# MuroBox-USB.net
KiCad netlist of a schematic drawn in EAGLE
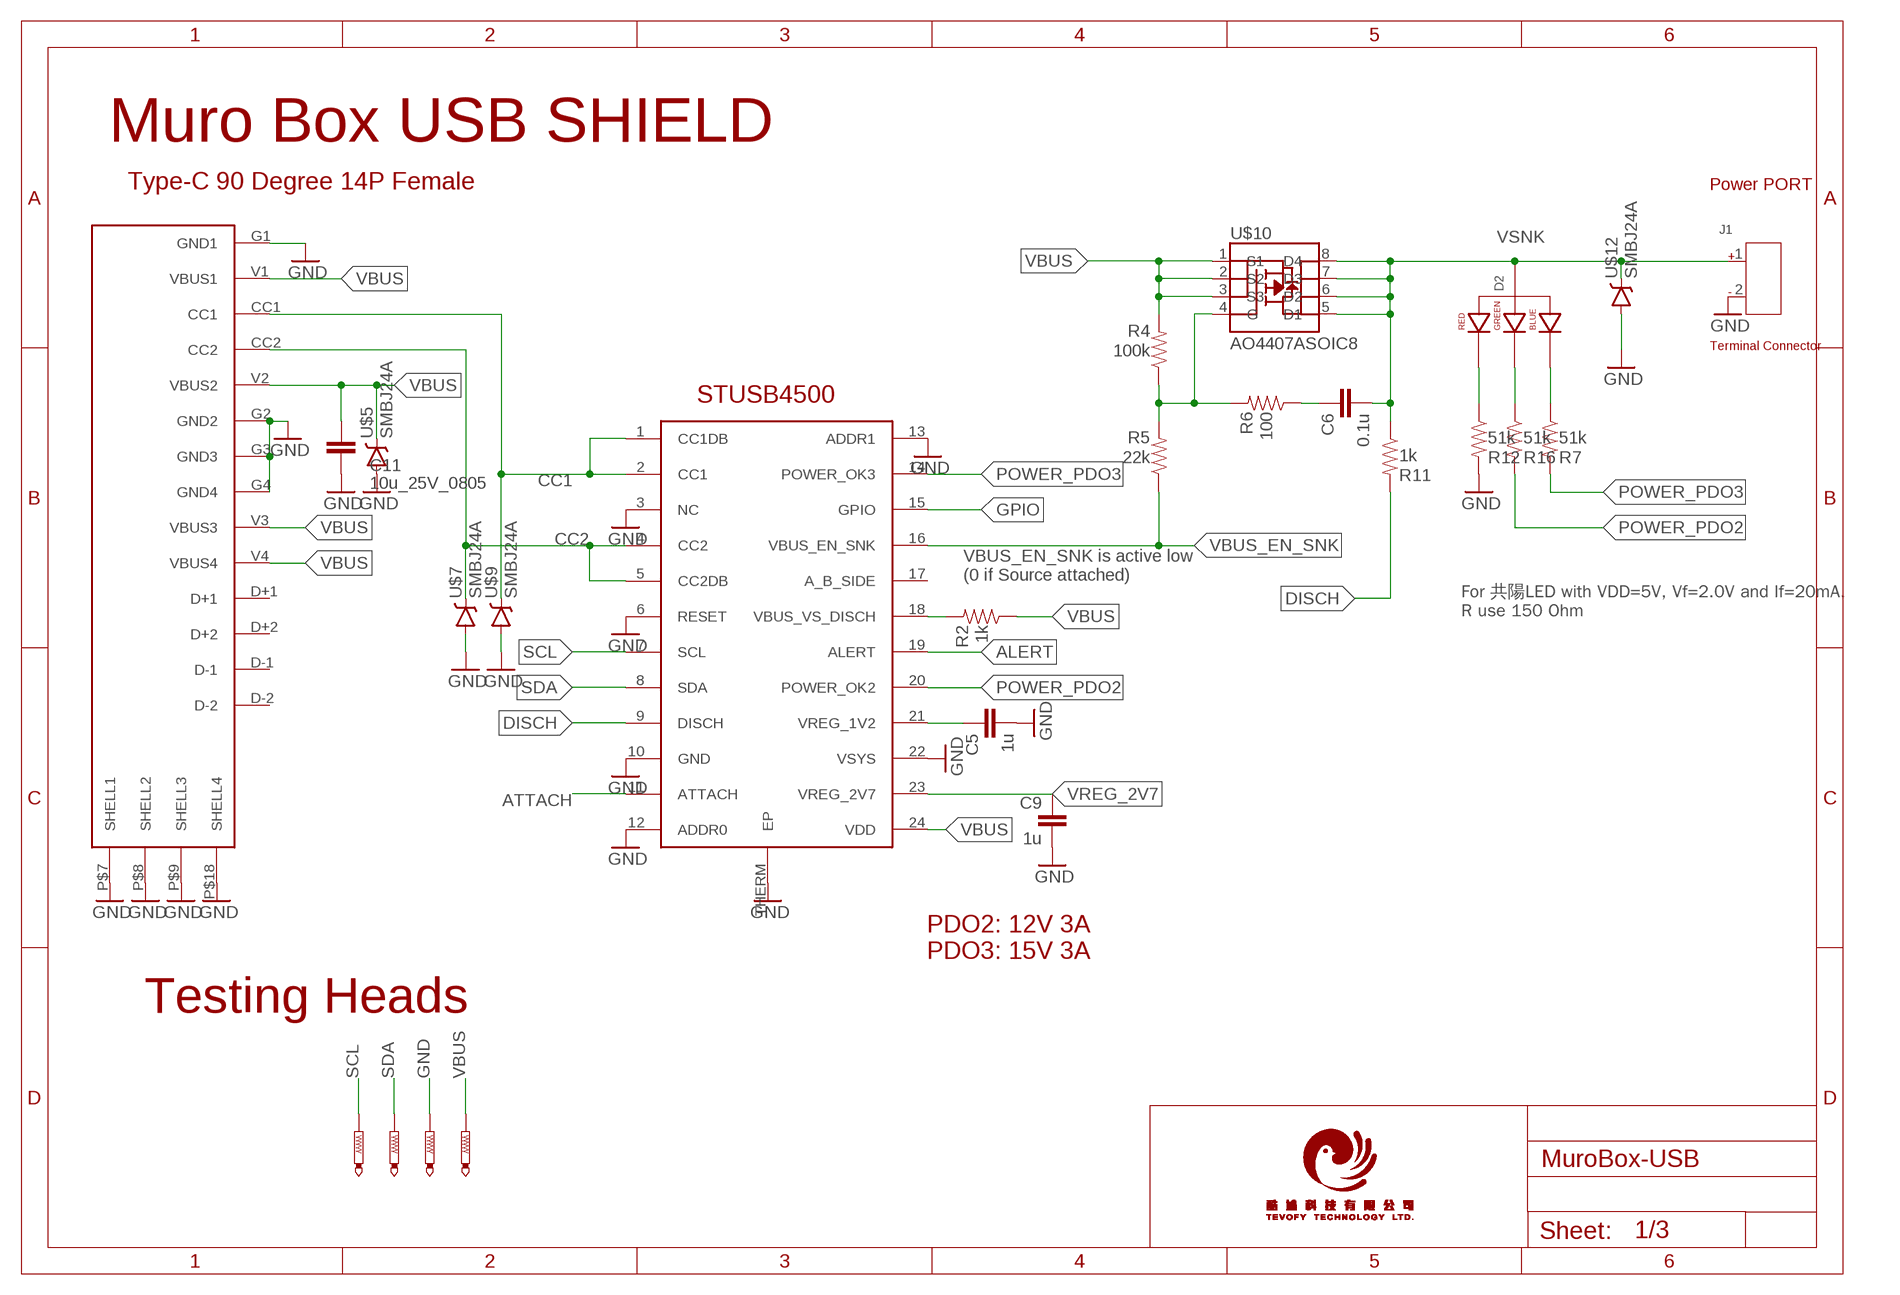
[diagram p0: schematic, sheet 1]
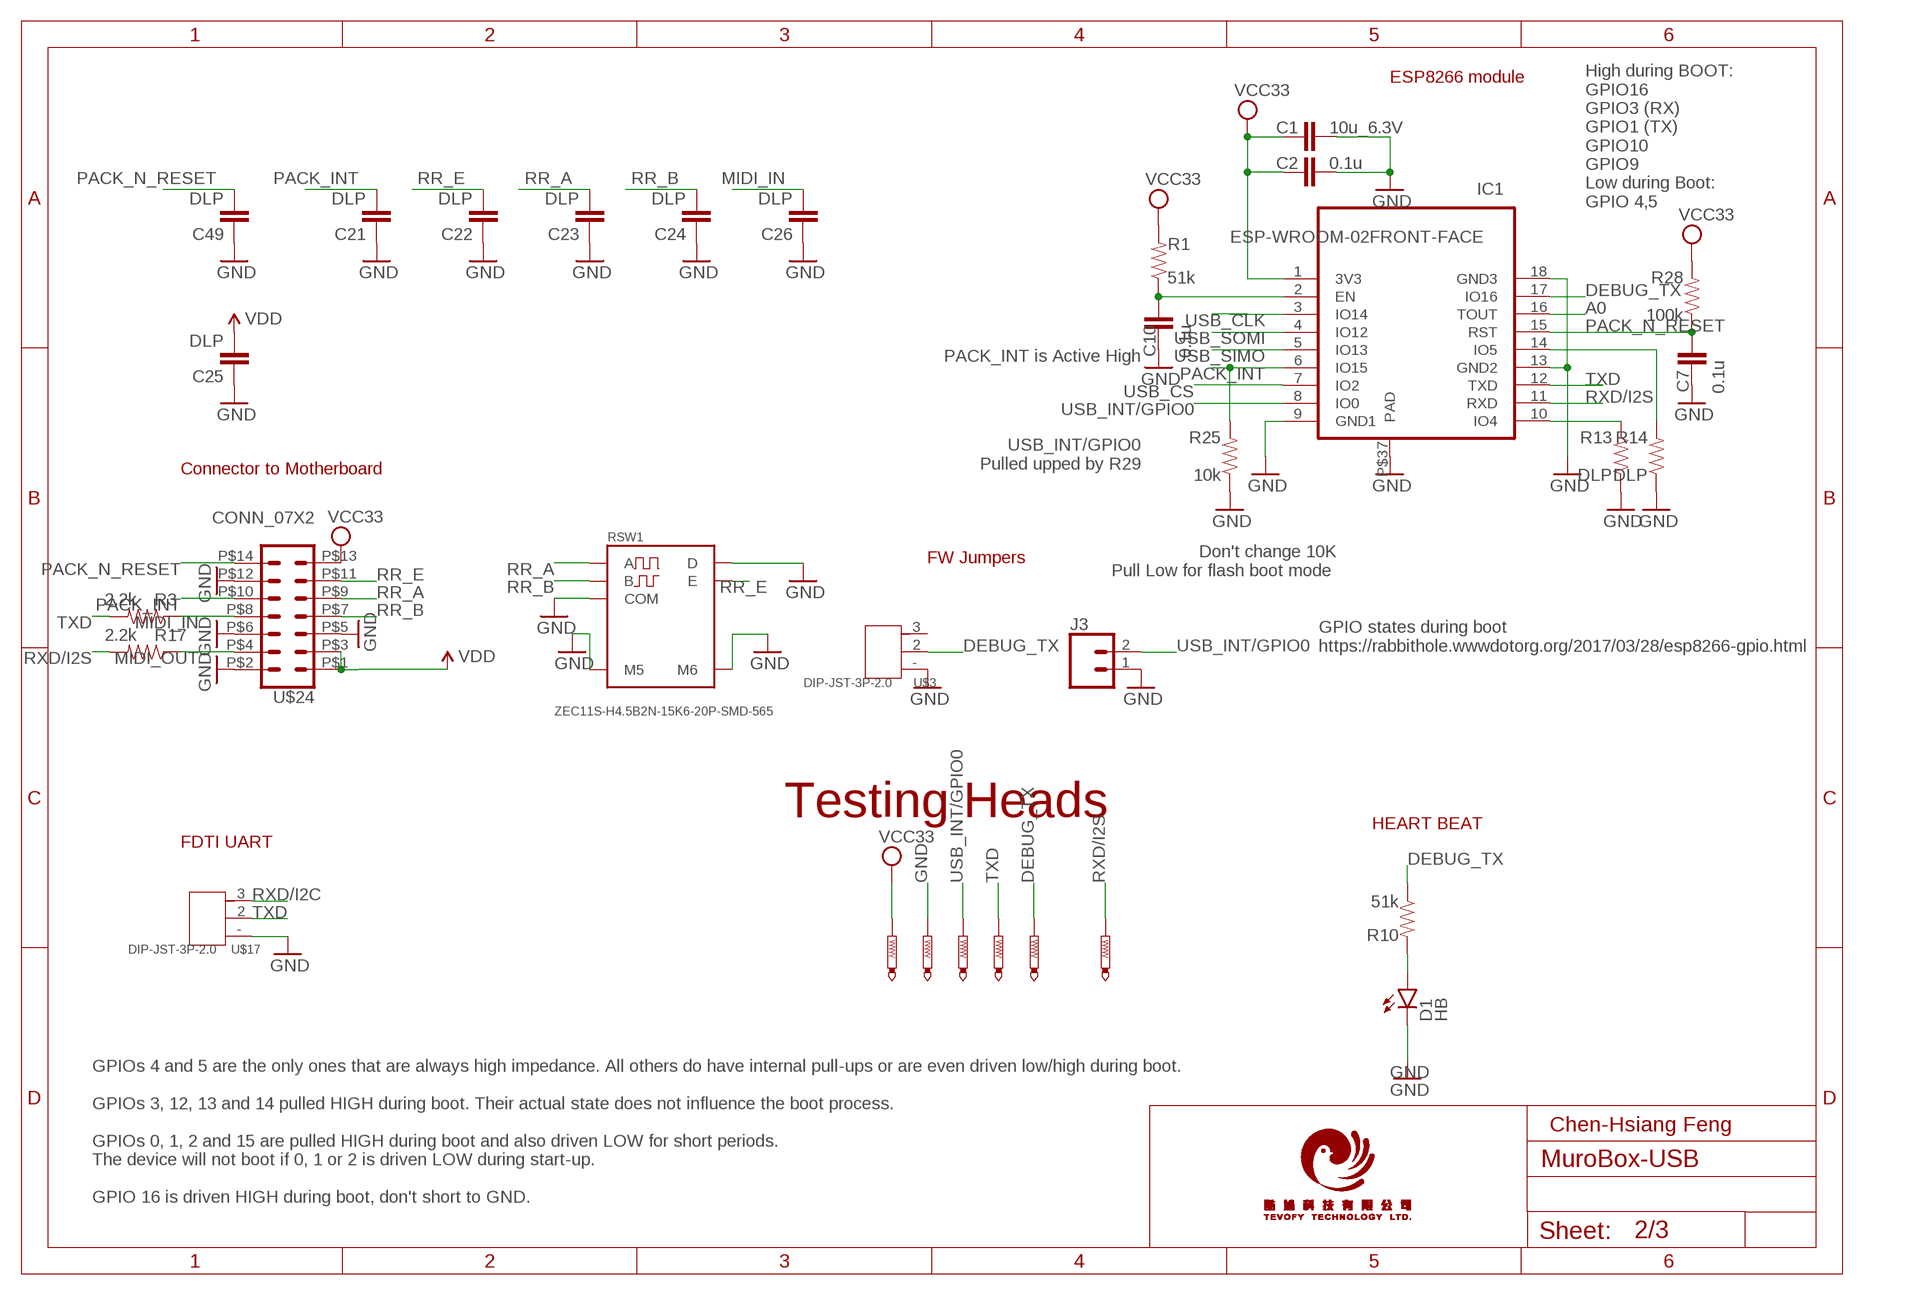
[diagram p1: schematic, sheet 2]
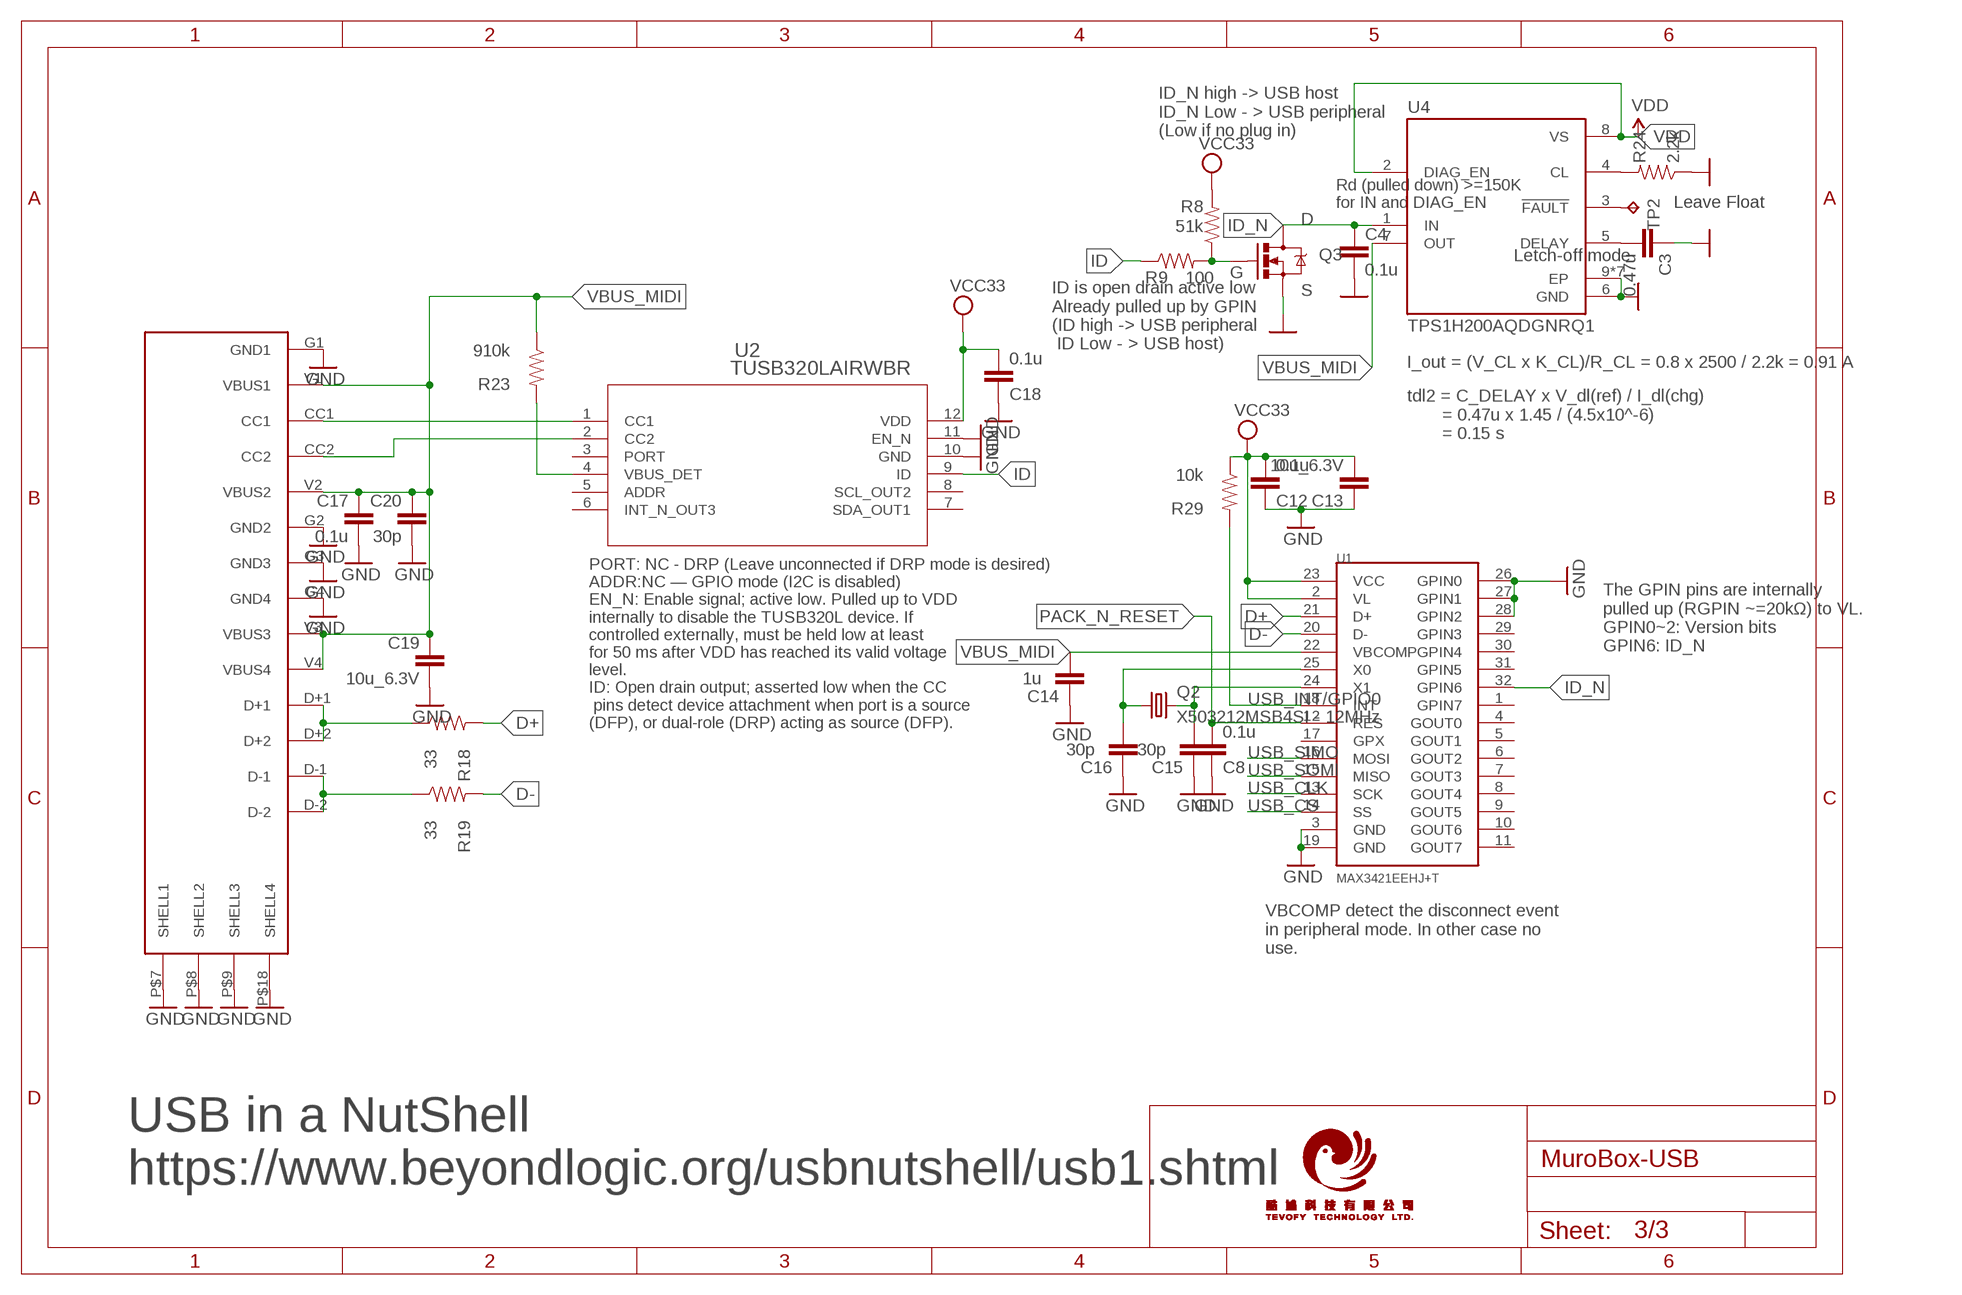
[diagram p2: schematic, sheet 3]

(export (version "E")
  (design (tool "Eeschema 10.0.6"))
  (components
    (comp (ref "C5")
      (value "1u")
      (footprint "eagle-import:0603-CAP")
      (libsource (lib "eagle-import") (part "CAP0603-CAP"))
    )
    (comp (ref "C6")
      (value "0.1u")
      (footprint "eagle-import:0603-CAP")
      (libsource (lib "eagle-import") (part "CAP0603-CAP"))
    )
    (comp (ref "C9")
      (value "1u")
      (footprint "eagle-import:0603-CAP")
      (libsource (lib "eagle-import") (part "CAP0603-CAP"))
    )
    (comp (ref "C11")
      (value "10u_25V_0805")
      (footprint "eagle-import:0805-CAP")
      (libsource (lib "eagle-import") (part "10UF10V10%(0805)"))
    )
    (comp (ref "D2")
      (value "LED-RGB-CA-THRUCLEAR")
      (footprint "eagle-import:LED-RGB-THRU")
      (libsource (lib "eagle-import") (part "LED-RGB-CA-THRUCLEAR"))
    )
    (comp (ref "J1")
      (value "DIP-SCREW-TERMINAL(2P-2.54)")
      (footprint "eagle-import:H2-2.54-5.48X6.3MM")
      (libsource (lib "eagle-import") (part "DIP-SCREW-TERMINAL(2P-2.54)"))
    )
    (comp (ref "R2")
      (value "1k")
      (footprint "eagle-import:0603-RES")
      (libsource (lib "eagle-import") (part "RESISTOR0603-RES"))
    )
    (comp (ref "R4")
      (value "100k")
      (footprint "eagle-import:0603-RES")
      (libsource (lib "eagle-import") (part "RESISTOR0603-RES"))
    )
    (comp (ref "R5")
      (value "22k")
      (footprint "eagle-import:0603-RES")
      (libsource (lib "eagle-import") (part "RESISTOR0603-RES"))
    )
    (comp (ref "R6")
      (value "100")
      (footprint "eagle-import:0603-RES")
      (libsource (lib "eagle-import") (part "RESISTOR0603-RES"))
    )
    (comp (ref "R7")
      (value "51k")
      (footprint "eagle-import:0603-RES")
      (libsource (lib "eagle-import") (part "RESISTOR0603-RES"))
    )
    (comp (ref "R11")
      (value "1k")
      (footprint "eagle-import:0603-RES")
      (libsource (lib "eagle-import") (part "RESISTOR0603-RES"))
    )
    (comp (ref "R12")
      (value "51k")
      (footprint "eagle-import:0603-RES")
      (libsource (lib "eagle-import") (part "RESISTOR0603-RES"))
    )
    (comp (ref "R16")
      (value "51k")
      (footprint "eagle-import:0603-RES")
      (libsource (lib "eagle-import") (part "RESISTOR0603-RES"))
    )
    (comp (ref "U$1")
      (value "STUSB4500")
      (footprint "eagle-import:QFN24")
      (libsource (lib "eagle-import") (part "STUSB4500"))
    )
    (comp (ref "U$5")
      (value "SMBJ24A")
      (footprint "eagle-import:SMB-DIODE")
      (libsource (lib "eagle-import") (part "SMBJ24A"))
    )
    (comp (ref "U$7")
      (value "SMBJ24A")
      (footprint "eagle-import:SMB-DIODE")
      (libsource (lib "eagle-import") (part "SMBJ24A"))
    )
    (comp (ref "U$9")
      (value "SMBJ24A")
      (footprint "eagle-import:SMB-DIODE")
      (libsource (lib "eagle-import") (part "SMBJ24A"))
    )
    (comp (ref "U$10")
      (value "AO4407ASOIC8")
      (footprint "eagle-import:SO08")
      (libsource (lib "eagle-import") (part "AO4407ASOIC8"))
    )
    (comp (ref "U$12")
      (value "SMBJ24A")
      (footprint "eagle-import:SMB-DIODE")
      (libsource (lib "eagle-import") (part "SMBJ24A"))
    )
    (comp (ref "U$22")
      (value "1PIN_TEST_PAD")
      (footprint "eagle-import:TP18R")
      (libsource (lib "eagle-import") (part "1PIN_TEST_PAD"))
    )
    (comp (ref "U$23")
      (value "1PIN_TEST_PAD")
      (footprint "eagle-import:TP18R")
      (libsource (lib "eagle-import") (part "1PIN_TEST_PAD"))
    )
    (comp (ref "U$25")
      (value "1PIN_TEST_PAD")
      (footprint "eagle-import:TP18R")
      (libsource (lib "eagle-import") (part "1PIN_TEST_PAD"))
    )
    (comp (ref "U$26")
      (value "1PIN_TEST_PAD")
      (footprint "eagle-import:TP18R")
      (libsource (lib "eagle-import") (part "1PIN_TEST_PAD"))
    )
    (comp (ref "U$27")
      (value "USB-TYPE-C-90D-12P")
      (footprint "eagle-import:USB-TYPE-C-90D-12P")
      (libsource (lib "eagle-import") (part "USB-TYPE-C-90D-12P"))
    )
    (comp (ref "C1")
      (value "10u_6.3V")
      (footprint "eagle-import:0603-CAP")
      (libsource (lib "eagle-import") (part "CAP0603-CAP"))
    )
    (comp (ref "C2")
      (value "0.1u")
      (footprint "eagle-import:0603-CAP")
      (libsource (lib "eagle-import") (part "CAP0603-CAP"))
    )
    (comp (ref "C7")
      (value "0.1u")
      (footprint "eagle-import:0603-CAP")
      (libsource (lib "eagle-import") (part "CAP0603-CAP"))
    )
    (comp (ref "C10")
      (value "0.1u")
      (footprint "eagle-import:0603-CAP")
      (libsource (lib "eagle-import") (part "CAP0603-CAP"))
    )
    (comp (ref "C21")
      (value "DLP")
      (footprint "eagle-import:0603-CAP")
      (libsource (lib "eagle-import") (part "CAP0603-CAP"))
    )
    (comp (ref "C22")
      (value "DLP")
      (footprint "eagle-import:0603-CAP")
      (libsource (lib "eagle-import") (part "CAP0603-CAP"))
    )
    (comp (ref "C23")
      (value "DLP")
      (footprint "eagle-import:0603-CAP")
      (libsource (lib "eagle-import") (part "CAP0603-CAP"))
    )
    (comp (ref "C24")
      (value "DLP")
      (footprint "eagle-import:0603-CAP")
      (libsource (lib "eagle-import") (part "CAP0603-CAP"))
    )
    (comp (ref "C25")
      (value "DLP")
      (footprint "eagle-import:0603-CAP")
      (libsource (lib "eagle-import") (part "CAP0603-CAP"))
    )
    (comp (ref "C26")
      (value "DLP")
      (footprint "eagle-import:0603-CAP")
      (libsource (lib "eagle-import") (part "CAP0603-CAP"))
    )
    (comp (ref "C49")
      (value "DLP")
      (footprint "eagle-import:0603-CAP")
      (libsource (lib "eagle-import") (part "CAP0603-CAP"))
    )
    (comp (ref "D1")
      (value "HB")
      (footprint "eagle-import:LED-0603")
      (libsource (lib "eagle-import") (part "LED-RED0603"))
    )
    (comp (ref "IC1")
      (value "ESP-WROOM-02FRONT-FACE")
      (footprint "eagle-import:ESP-WROOM-02_FRONT-FACE")
      (fields (field (name "PART_NUMBER") "ESP-WROOM-02"))
      (libsource (lib "eagle-import") (part "ESP-WROOM-02FRONT-FACE"))
    )
    (comp (ref "J3")
      (value "CONN_02LOCK")
      (footprint "eagle-import:1X02_LOCK")
      (libsource (lib "eagle-import") (part "CONN_02LOCK"))
    )
    (comp (ref "R1")
      (value "51k")
      (footprint "eagle-import:0603-RES")
      (libsource (lib "eagle-import") (part "RESISTOR0603-RES"))
    )
    (comp (ref "R3")
      (value "2.2k")
      (footprint "eagle-import:0603-RES")
      (libsource (lib "eagle-import") (part "RESISTOR0603-RES"))
    )
    (comp (ref "R10")
      (value "51k")
      (footprint "eagle-import:0603-RES")
      (libsource (lib "eagle-import") (part "RESISTOR0603-RES"))
    )
    (comp (ref "R13")
      (value "DLP")
      (footprint "eagle-import:0603-RES")
      (libsource (lib "eagle-import") (part "RESISTOR0603-RES"))
    )
    (comp (ref "R14")
      (value "DLP")
      (footprint "eagle-import:0603-RES")
      (libsource (lib "eagle-import") (part "RESISTOR0603-RES"))
    )
    (comp (ref "R17")
      (value "2.2k")
      (footprint "eagle-import:0603-RES")
      (libsource (lib "eagle-import") (part "RESISTOR0603-RES"))
    )
    (comp (ref "R25")
      (value "10k")
      (footprint "eagle-import:0603-RES")
      (libsource (lib "eagle-import") (part "RESISTOR0603-RES"))
    )
    (comp (ref "R28")
      (value "100k")
      (footprint "eagle-import:0603-RES")
      (libsource (lib "eagle-import") (part "RESISTOR0603-RES"))
    )
    (comp (ref "RSW1")
      (value "ZEC11S-H4.5B2N-15K6-20P-SMD-565")
      (footprint "eagle-import:EC11-CHINA")
      (libsource (lib "eagle-import") (part "SW-EC11-CHINA"))
    )
    (comp (ref "U$3")
      (value "DIP-JST-3P-2.0")
      (footprint "eagle-import:H3-2.0-8X4.5MM")
      (libsource (lib "eagle-import") (part "DIP-JST-3P-2.0"))
    )
    (comp (ref "U$4")
      (value "1PIN_TEST_PAD")
      (footprint "eagle-import:TP18R")
      (libsource (lib "eagle-import") (part "1PIN_TEST_PAD"))
    )
    (comp (ref "U$8")
      (value "1PIN_TEST_PAD")
      (footprint "eagle-import:TP18R")
      (libsource (lib "eagle-import") (part "1PIN_TEST_PAD"))
    )
    (comp (ref "U$14")
      (value "1PIN_TEST_PAD")
      (footprint "eagle-import:TP18R")
      (libsource (lib "eagle-import") (part "1PIN_TEST_PAD"))
    )
    (comp (ref "U$16")
      (value "1PIN_TEST_PAD")
      (footprint "eagle-import:TP18R")
      (libsource (lib "eagle-import") (part "1PIN_TEST_PAD"))
    )
    (comp (ref "U$17")
      (value "DIP-JST-3P-2.0")
      (footprint "eagle-import:H3-2.0-8X4.5MM")
      (libsource (lib "eagle-import") (part "DIP-JST-3P-2.0"))
    )
    (comp (ref "U$18")
      (value "1PIN_TEST_PAD")
      (footprint "eagle-import:TP18R")
      (libsource (lib "eagle-import") (part "1PIN_TEST_PAD"))
    )
    (comp (ref "U$19")
      (value "1PIN_TEST_PAD")
      (footprint "eagle-import:TP18R")
      (libsource (lib "eagle-import") (part "1PIN_TEST_PAD"))
    )
    (comp (ref "U$24")
      (value "CONN_07X2")
      (footprint "eagle-import:PHB-7X2")
      (libsource (lib "eagle-import") (part "CONN_07X2"))
    )
    (comp (ref "C3")
      (value "0.47u")
      (footprint "eagle-import:0603-CAP")
      (libsource (lib "eagle-import") (part "CAP0603-CAP"))
    )
    (comp (ref "C4")
      (value "0.1u")
      (footprint "eagle-import:0603-CAP")
      (libsource (lib "eagle-import") (part "CAP0603-CAP"))
    )
    (comp (ref "C8")
      (value "0.1u")
      (footprint "eagle-import:0603-CAP")
      (libsource (lib "eagle-import") (part "CAP0603-CAP"))
    )
    (comp (ref "C12")
      (value "0.1u")
      (footprint "eagle-import:0603-CAP")
      (libsource (lib "eagle-import") (part "CAP0603-CAP"))
    )
    (comp (ref "C13")
      (value "10u_6.3V")
      (footprint "eagle-import:0603-CAP")
      (libsource (lib "eagle-import") (part "CAP0603-CAP"))
    )
    (comp (ref "C14")
      (value "1u")
      (footprint "eagle-import:0603-CAP")
      (libsource (lib "eagle-import") (part "CAP0603-CAP"))
    )
    (comp (ref "C15")
      (value "30p")
      (footprint "eagle-import:0603-CAP")
      (libsource (lib "eagle-import") (part "CAP0603-CAP"))
    )
    (comp (ref "C16")
      (value "30p")
      (footprint "eagle-import:0603-CAP")
      (libsource (lib "eagle-import") (part "CAP0603-CAP"))
    )
    (comp (ref "C17")
      (value "0.1u")
      (footprint "eagle-import:0603-CAP")
      (libsource (lib "eagle-import") (part "CAP0603-CAP"))
    )
    (comp (ref "C18")
      (value "0.1u")
      (footprint "eagle-import:0603-CAP")
      (libsource (lib "eagle-import") (part "CAP0603-CAP"))
    )
    (comp (ref "C19")
      (value "10u_6.3V")
      (footprint "eagle-import:0603-CAP")
      (libsource (lib "eagle-import") (part "CAP0603-CAP"))
    )
    (comp (ref "C20")
      (value "30p")
      (footprint "eagle-import:0603-CAP")
      (libsource (lib "eagle-import") (part "CAP0603-CAP"))
    )
    (comp (ref "Q2")
      (value "X503212MSB4SI - 12MHz")
      (footprint "eagle-import:CRYSTAL-SMD-5X3")
      (libsource (lib "eagle-import") (part "CRYSTAL5X3"))
    )
    (comp (ref "Q3")
      (value "AO3400A_X0RB48")
      (footprint "eagle-import:SOT23")
      (libsource (lib "eagle-import") (part "AO3400A_X0RB48SOT23"))
    )
    (comp (ref "R8")
      (value "51k")
      (footprint "eagle-import:0603-RES")
      (libsource (lib "eagle-import") (part "RESISTOR0603-RES"))
    )
    (comp (ref "R9")
      (value "100")
      (footprint "eagle-import:0603-RES")
      (libsource (lib "eagle-import") (part "RESISTOR0603-RES"))
    )
    (comp (ref "R18")
      (value "33")
      (footprint "eagle-import:0603-RES")
      (libsource (lib "eagle-import") (part "RESISTOR0603-RES"))
    )
    (comp (ref "R19")
      (value "33")
      (footprint "eagle-import:0603-RES")
      (libsource (lib "eagle-import") (part "RESISTOR0603-RES"))
    )
    (comp (ref "R23")
      (value "910k")
      (footprint "eagle-import:0603-RES")
      (libsource (lib "eagle-import") (part "RESISTOR0603-RES"))
    )
    (comp (ref "R24")
      (value "2.2k")
      (footprint "eagle-import:0603-RES")
      (libsource (lib "eagle-import") (part "RESISTOR0603-RES"))
    )
    (comp (ref "R29")
      (value "10k")
      (footprint "eagle-import:0603-RES")
      (libsource (lib "eagle-import") (part "RESISTOR0603-RES"))
    )
    (comp (ref "TP2")
      (value "TPB1,27")
      (footprint "eagle-import:B1,27")
      (libsource (lib "eagle-import") (part "TPB1,27"))
    )
    (comp (ref "U$6")
      (value "USB-TYPE-C-90D-12P")
      (footprint "eagle-import:USB-TYPE-C-90D-12P")
      (libsource (lib "eagle-import") (part "USB-TYPE-C-90D-12P"))
    )
    (comp (ref "U1")
      (value "MAX3421EEHJ+T")
      (footprint "eagle-import:TQFP32-5MM")
      (libsource (lib "eagle-import") (part "MAX3421ESMD"))
    )
    (comp (ref "U2")
      (value "TUSB320LAIRWBR")
      (footprint "eagle-import:RWB0012A_TEX")
      (fields (field (name "COPYRIGHT") "Copyright (C) 2018 Accelerated Designs. All rights reserved"))
      (libsource (lib "eagle-import") (part "TUSB320LAIRWBR"))
    )
    (comp (ref "U4")
      (value "TPS1H200AQDGNRQ1")
      (footprint "eagle-import:SOP65P490X110-9N")
      (fields (field (name "MF") "Texas Instruments"))
      (libsource (lib "eagle-import") (part "TPS1H200AQDGNRQ1"))
    )
  )
  (nets
    (net (code "1") (name "A0") (class "Default")
      (node (ref "IC1") (pin "16") (pinfunction "TOUT_16") (pintype "bidirectional"))
    )
    (net (code "2") (name "ALERT") (class "Default")
      (node (ref "U$1") (pin "19") (pinfunction "ALERT_19") (pintype "bidirectional"))
    )
    (net (code "3") (name "ATTACH") (class "Default")
      (node (ref "U$1") (pin "11") (pinfunction "ATTACH_11") (pintype "bidirectional"))
    )
    (net (code "4") (name "CC1") (class "Default")
      (node (ref "U$1") (pin "1") (pinfunction "CC1DB_1") (pintype "bidirectional"))
      (node (ref "U$1") (pin "2") (pinfunction "CC1_2") (pintype "bidirectional"))
      (node (ref "U$27") (pin "CC1") (pinfunction "CC1_CC1") (pintype "bidirectional"))
      (node (ref "U$9") (pin "C") (pinfunction "C_C") (pintype "passive"))
    )
    (net (code "5") (name "CC2") (class "Default")
      (node (ref "U$1") (pin "4") (pinfunction "CC2_4") (pintype "bidirectional"))
      (node (ref "U$1") (pin "5") (pinfunction "CC2DB_5") (pintype "bidirectional"))
      (node (ref "U$27") (pin "CC2") (pinfunction "CC2_CC2") (pintype "bidirectional"))
      (node (ref "U$7") (pin "C") (pinfunction "C_C") (pintype "passive"))
    )
    (net (code "6") (name "D+") (class "Default")
      (node (ref "R18") (pin "2") (pinfunction "2_2") (pintype "passive"))
      (node (ref "U1") (pin "21") (pinfunction "D+_21") (pintype "bidirectional"))
    )
    (net (code "7") (name "D-") (class "Default")
      (node (ref "R19") (pin "2") (pinfunction "2_2") (pintype "passive"))
      (node (ref "U1") (pin "20") (pinfunction "D-_20") (pintype "bidirectional"))
    )
    (net (code "8") (name "DEBUG_TX") (class "Default")
      (node (ref "IC1") (pin "17") (pinfunction "IO16_17") (pintype "bidirectional"))
      (node (ref "R10") (pin "1") (pinfunction "1_1") (pintype "passive"))
      (node (ref "U$3") (pin "2") (pinfunction "P$2_2") (pintype "bidirectional"))
      (node (ref "U$4") (pin "TP") (pinfunction "TP_TP") (pintype "input"))
    )
    (net (code "9") (name "DISCH") (class "Default")
      (node (ref "R11") (pin "2") (pinfunction "2_2") (pintype "passive"))
      (node (ref "U$1") (pin "9") (pinfunction "DISCH_9") (pintype "bidirectional"))
    )
    (net (code "10") (name "GND") (class "Default")
      (node (ref "C1") (pin "2") (pinfunction "2_2") (pintype "passive"))
      (node (ref "C10") (pin "1") (pinfunction "1_1") (pintype "passive"))
      (node (ref "C11") (pin "1") (pinfunction "1_1") (pintype "passive"))
      (node (ref "C12") (pin "1") (pinfunction "1_1") (pintype "passive"))
      (node (ref "C13") (pin "1") (pinfunction "1_1") (pintype "passive"))
      (node (ref "C14") (pin "1") (pinfunction "1_1") (pintype "passive"))
      (node (ref "C15") (pin "1") (pinfunction "1_1") (pintype "passive"))
      (node (ref "C16") (pin "1") (pinfunction "1_1") (pintype "passive"))
      (node (ref "C17") (pin "1") (pinfunction "1_1") (pintype "passive"))
      (node (ref "C18") (pin "1") (pinfunction "1_1") (pintype "passive"))
      (node (ref "C19") (pin "1") (pinfunction "1_1") (pintype "passive"))
      (node (ref "C2") (pin "2") (pinfunction "2_2") (pintype "passive"))
      (node (ref "C20") (pin "1") (pinfunction "1_1") (pintype "passive"))
      (node (ref "C21") (pin "1") (pinfunction "1_1") (pintype "passive"))
      (node (ref "C22") (pin "1") (pinfunction "1_1") (pintype "passive"))
      (node (ref "C23") (pin "1") (pinfunction "1_1") (pintype "passive"))
      (node (ref "C24") (pin "1") (pinfunction "1_1") (pintype "passive"))
      (node (ref "C25") (pin "1") (pinfunction "1_1") (pintype "passive"))
      (node (ref "C26") (pin "1") (pinfunction "1_1") (pintype "passive"))
      (node (ref "C3") (pin "1") (pinfunction "1_1") (pintype "passive"))
      (node (ref "C4") (pin "2") (pinfunction "2_2") (pintype "passive"))
      (node (ref "C49") (pin "1") (pinfunction "1_1") (pintype "passive"))
      (node (ref "C5") (pin "1") (pinfunction "1_1") (pintype "passive"))
      (node (ref "C7") (pin "1") (pinfunction "1_1") (pintype "passive"))
      (node (ref "C8") (pin "1") (pinfunction "1_1") (pintype "passive"))
      (node (ref "C9") (pin "1") (pinfunction "1_1") (pintype "passive"))
      (node (ref "D1") (pin "C") (pinfunction "C_C") (pintype "passive"))
      (node (ref "IC1") (pin "13") (pinfunction "GND2_13") (pintype "power_in"))
      (node (ref "IC1") (pin "18") (pinfunction "GND3_18") (pintype "power_in"))
      (node (ref "IC1") (pin "9") (pinfunction "GND1_9") (pintype "power_in"))
      (node (ref "IC1") (pin "P$37") (pinfunction "PAD_P$37") (pintype "passive"))
      (node (ref "J1") (pin "2") (pinfunction "2_2") (pintype "bidirectional"))
      (node (ref "J3") (pin "1") (pinfunction "1_1") (pintype "passive"))
      (node (ref "Q3") (pin "2") (pinfunction "S_2") (pintype "passive"))
      (node (ref "R12") (pin "2") (pinfunction "2_2") (pintype "passive"))
      (node (ref "R13") (pin "1") (pinfunction "1_1") (pintype "passive"))
      (node (ref "R14") (pin "1") (pinfunction "1_1") (pintype "passive"))
      (node (ref "R24") (pin "1") (pinfunction "1_1") (pintype "passive"))
      (node (ref "R25") (pin "1") (pinfunction "1_1") (pintype "passive"))
      (node (ref "RSW1") (pin "C") (pinfunction "COM_C") (pintype "bidirectional"))
      (node (ref "RSW1") (pin "M5") (pinfunction "M5_M5") (pintype "bidirectional"))
      (node (ref "RSW1") (pin "M6") (pinfunction "M6_M6") (pintype "bidirectional"))
      (node (ref "RSW1") (pin "SW1") (pinfunction "D_SW1") (pintype "bidirectional"))
      (node (ref "U$1") (pin "10") (pinfunction "GND_10") (pintype "bidirectional"))
      (node (ref "U$1") (pin "12") (pinfunction "ADDR0_12") (pintype "bidirectional"))
      (node (ref "U$1") (pin "13") (pinfunction "ADDR1_13") (pintype "bidirectional"))
      (node (ref "U$1") (pin "22") (pinfunction "VSYS_22") (pintype "bidirectional"))
      (node (ref "U$1") (pin "3") (pinfunction "NC_3") (pintype "bidirectional"))
      (node (ref "U$1") (pin "6") (pinfunction "RESET_6") (pintype "bidirectional"))
      (node (ref "U$1") (pin "THERM") (pinfunction "EP_THERM") (pintype "bidirectional"))
      (node (ref "U$12") (pin "A") (pinfunction "A_A") (pintype "passive"))
      (node (ref "U$17") (pin "-") (pinfunction "P$1_-") (pintype "bidirectional"))
      (node (ref "U$18") (pin "TP") (pinfunction "TP_TP") (pintype "input"))
      (node (ref "U$24") (pin "P$12") (pinfunction "12_P$12") (pintype "passive"))
      (node (ref "U$24") (pin "P$2") (pinfunction "2_P$2") (pintype "passive"))
      (node (ref "U$24") (pin "P$5") (pinfunction "5_P$5") (pintype "passive"))
      (node (ref "U$24") (pin "P$6") (pinfunction "6_P$6") (pintype "passive"))
      (node (ref "U$26") (pin "TP") (pinfunction "TP_TP") (pintype "input"))
      (node (ref "U$27") (pin "G1") (pinfunction "GND1_G1") (pintype "bidirectional"))
      (node (ref "U$27") (pin "G2") (pinfunction "GND2_G2") (pintype "bidirectional"))
      (node (ref "U$27") (pin "G3") (pinfunction "GND3_G3") (pintype "bidirectional"))
      (node (ref "U$27") (pin "G4") (pinfunction "GND4_G4") (pintype "bidirectional"))
      (node (ref "U$27") (pin "P$18") (pinfunction "SHELL4_P$18") (pintype "bidirectional"))
      (node (ref "U$27") (pin "P$7") (pinfunction "SHELL1_P$7") (pintype "bidirectional"))
      (node (ref "U$27") (pin "P$8") (pinfunction "SHELL2_P$8") (pintype "bidirectional"))
      (node (ref "U$27") (pin "P$9") (pinfunction "SHELL3_P$9") (pintype "bidirectional"))
      (node (ref "U$3") (pin "-") (pinfunction "P$1_-") (pintype "bidirectional"))
      (node (ref "U$5") (pin "A") (pinfunction "A_A") (pintype "passive"))
      (node (ref "U$6") (pin "G1") (pinfunction "GND1_G1") (pintype "bidirectional"))
      (node (ref "U$6") (pin "G2") (pinfunction "GND2_G2") (pintype "bidirectional"))
      (node (ref "U$6") (pin "G3") (pinfunction "GND3_G3") (pintype "bidirectional"))
      (node (ref "U$6") (pin "G4") (pinfunction "GND4_G4") (pintype "bidirectional"))
      (node (ref "U$6") (pin "P$18") (pinfunction "SHELL4_P$18") (pintype "bidirectional"))
      (node (ref "U$6") (pin "P$7") (pinfunction "SHELL1_P$7") (pintype "bidirectional"))
      (node (ref "U$6") (pin "P$8") (pinfunction "SHELL2_P$8") (pintype "bidirectional"))
      (node (ref "U$6") (pin "P$9") (pinfunction "SHELL3_P$9") (pintype "bidirectional"))
      (node (ref "U$7") (pin "A") (pinfunction "A_A") (pintype "passive"))
      (node (ref "U$9") (pin "A") (pinfunction "A_A") (pintype "passive"))
      (node (ref "U1") (pin "19") (pinfunction "GND_19") (pintype "bidirectional"))
      (node (ref "U1") (pin "26") (pinfunction "GPIN0_26") (pintype "bidirectional"))
      (node (ref "U1") (pin "27") (pinfunction "GPIN1_27") (pintype "bidirectional"))
      (node (ref "U1") (pin "28") (pinfunction "GPIN2_28") (pintype "bidirectional"))
      (node (ref "U1") (pin "3") (pinfunction "GND_3") (pintype "bidirectional"))
      (node (ref "U2") (pin "10") (pinfunction "GND_10") (pintype "power_in"))
      (node (ref "U2") (pin "11") (pinfunction "EN_N_11") (pintype "input"))
      (node (ref "U4") (pin "6") (pinfunction "GND_6") (pintype "power_in"))
      (node (ref "U4") (pin "9") (pinfunction "EP_9") (pintype "passive"))
      (node (ref "U4") (pin "9_1") (pinfunction "EP_9_1") (pintype "passive"))
      (node (ref "U4") (pin "9_2") (pinfunction "EP_9_2") (pintype "passive"))
      (node (ref "U4") (pin "9_3") (pinfunction "EP_9_3") (pintype "passive"))
      (node (ref "U4") (pin "9_4") (pinfunction "EP_9_4") (pintype "passive"))
      (node (ref "U4") (pin "9_5") (pinfunction "EP_9_5") (pintype "passive"))
      (node (ref "U4") (pin "9_6") (pinfunction "EP_9_6") (pintype "passive"))
    )
    (net (code "11") (name "GPIO") (class "Default")
      (node (ref "U$1") (pin "15") (pinfunction "GPIO_15") (pintype "bidirectional"))
    )
    (net (code "12") (name "ID") (class "Default")
      (node (ref "R9") (pin "1") (pinfunction "1_1") (pintype "passive"))
      (node (ref "U2") (pin "9") (pinfunction "ID_9") (pintype "open_collector"))
    )
    (net (code "13") (name "ID_N") (class "Default")
      (node (ref "C4") (pin "1") (pinfunction "1_1") (pintype "passive"))
      (node (ref "Q3") (pin "3") (pinfunction "D_3") (pintype "passive"))
      (node (ref "U1") (pin "32") (pinfunction "GPIN6_32") (pintype "bidirectional"))
      (node (ref "U4") (pin "1") (pinfunction "IN_1") (pintype "input"))
    )
    (net (code "14") (name "MIDI_IN") (class "Default")
      (node (ref "C26") (pin "2") (pinfunction "2_2") (pintype "passive"))
      (node (ref "R3") (pin "1") (pinfunction "1_1") (pintype "passive"))
      (node (ref "U$24") (pin "P$8") (pinfunction "8_P$8") (pintype "passive"))
    )
    (net (code "15") (name "MIDI_OUT") (class "Default")
      (node (ref "R17") (pin "1") (pinfunction "1_1") (pintype "passive"))
      (node (ref "U$24") (pin "P$4") (pinfunction "4_P$4") (pintype "passive"))
    )
    (net (code "16") (name "Net-(C6-Pad2)") (class "Default")
      (node (ref "C6") (pin "2") (pinfunction "2_2") (pintype "passive"))
      (node (ref "R6") (pin "1") (pinfunction "1_1") (pintype "passive"))
    )
    (net (code "17") (name "Net-(D1-PadA)") (class "Default")
      (node (ref "D1") (pin "A") (pinfunction "A_A") (pintype "passive"))
      (node (ref "R10") (pin "2") (pinfunction "2_2") (pintype "passive"))
    )
    (net (code "18") (name "Net-(D2-BLUE_CATHODE)") (class "Default")
      (node (ref "D2") (pin "4") (pinfunction "BLUE_CATHODE_4") (pintype "bidirectional"))
      (node (ref "R7") (pin "1") (pinfunction "1_1") (pintype "passive"))
    )
    (net (code "19") (name "Net-(D2-GREEN_CATHODE)") (class "Default")
      (node (ref "D2") (pin "3") (pinfunction "GREEN_CATHODE_3") (pintype "bidirectional"))
      (node (ref "R16") (pin "1") (pinfunction "1_1") (pintype "passive"))
    )
    (net (code "20") (name "Net-(D2-RED_CATHODE)") (class "Default")
      (node (ref "D2") (pin "1") (pinfunction "RED_CATHODE_1") (pintype "bidirectional"))
      (node (ref "R12") (pin "1") (pinfunction "1_1") (pintype "passive"))
    )
    (net (code "21") (name "Net-(IC1-EN)") (class "Default")
      (node (ref "C10") (pin "2") (pinfunction "2_2") (pintype "passive"))
      (node (ref "IC1") (pin "2") (pinfunction "EN_2") (pintype "bidirectional"))
      (node (ref "R1") (pin "1") (pinfunction "1_1") (pintype "passive"))
    )
    (net (code "22") (name "Net-(IC1-IO4)") (class "Default")
      (node (ref "IC1") (pin "10") (pinfunction "IO4_10") (pintype "bidirectional"))
      (node (ref "R13") (pin "2") (pinfunction "2_2") (pintype "passive"))
    )
    (net (code "23") (name "Net-(IC1-IO5)") (class "Default")
      (node (ref "IC1") (pin "14") (pinfunction "IO5_14") (pintype "open_collector"))
      (node (ref "R14") (pin "2") (pinfunction "2_2") (pintype "passive"))
    )
    (net (code "24") (name "Net-(Q2-2)") (class "Default")
      (node (ref "C15") (pin "2") (pinfunction "2_2") (pintype "passive"))
      (node (ref "Q2") (pin "3") (pinfunction "2_3") (pintype "passive"))
      (node (ref "U1") (pin "24") (pinfunction "X1_24") (pintype "bidirectional"))
    )
    (net (code "25") (name "Net-(Q3-G)") (class "Default")
      (node (ref "Q3") (pin "1") (pinfunction "G_1") (pintype "passive"))
      (node (ref "R8") (pin "1") (pinfunction "1_1") (pintype "passive"))
      (node (ref "R9") (pin "2") (pinfunction "2_2") (pintype "passive"))
    )
    (net (code "26") (name "Net-(R18-Pad1)") (class "Default")
      (node (ref "R18") (pin "1") (pinfunction "1_1") (pintype "passive"))
      (node (ref "U$6") (pin "D+1") (pinfunction "D+1_D+1") (pintype "bidirectional"))
      (node (ref "U$6") (pin "D+2") (pinfunction "D+2_D+2") (pintype "bidirectional"))
    )
    (net (code "27") (name "Net-(R19-Pad1)") (class "Default")
      (node (ref "R19") (pin "1") (pinfunction "1_1") (pintype "passive"))
      (node (ref "U$6") (pin "D-1") (pinfunction "D-1_D-1") (pintype "bidirectional"))
      (node (ref "U$6") (pin "D-2") (pinfunction "D-2_D-2") (pintype "bidirectional"))
    )
    (net (code "28") (name "Net-(U$1-VBUS_VS_DISCH)") (class "Default")
      (node (ref "R2") (pin "2") (pinfunction "2_2") (pintype "passive"))
      (node (ref "U$1") (pin "18") (pinfunction "VBUS_VS_DISCH_18") (pintype "bidirectional"))
    )
    (net (code "29") (name "Net-(U$1-VREG_1V2)") (class "Default")
      (node (ref "C5") (pin "2") (pinfunction "2_2") (pintype "passive"))
      (node (ref "U$1") (pin "21") (pinfunction "VREG_1V2_21") (pintype "bidirectional"))
    )
    (net (code "30") (name "Net-(U$10-G)") (class "Default")
      (node (ref "R4") (pin "1") (pinfunction "1_1") (pintype "passive"))
      (node (ref "R5") (pin "2") (pinfunction "2_2") (pintype "passive"))
      (node (ref "R6") (pin "2") (pinfunction "2_2") (pintype "passive"))
      (node (ref "U$10") (pin "4") (pinfunction "G_4") (pintype "bidirectional"))
    )
    (net (code "31") (name "Net-(U1-X0)") (class "Default")
      (node (ref "C16") (pin "2") (pinfunction "2_2") (pintype "passive"))
      (node (ref "Q2") (pin "1") (pinfunction "1_1") (pintype "passive"))
      (node (ref "U1") (pin "25") (pinfunction "X0_25") (pintype "bidirectional"))
    )
    (net (code "32") (name "Net-(U2-CC1)") (class "Default")
      (node (ref "U$6") (pin "CC1") (pinfunction "CC1_CC1") (pintype "bidirectional"))
      (node (ref "U2") (pin "1") (pinfunction "CC1_1") (pintype "bidirectional"))
    )
    (net (code "33") (name "Net-(U2-CC2)") (class "Default")
      (node (ref "U$6") (pin "CC2") (pinfunction "CC2_CC2") (pintype "bidirectional"))
      (node (ref "U2") (pin "2") (pinfunction "CC2_2") (pintype "bidirectional"))
    )
    (net (code "34") (name "Net-(U2-VBUS_DET)") (class "Default")
      (node (ref "R23") (pin "2") (pinfunction "2_2") (pintype "passive"))
      (node (ref "U2") (pin "4") (pinfunction "VBUS_DET_4") (pintype "input"))
    )
    (net (code "35") (name "Net-(U4-CL)") (class "Default")
      (node (ref "R24") (pin "2") (pinfunction "2_2") (pintype "passive"))
      (node (ref "U4") (pin "4") (pinfunction "CL_4") (pintype "output"))
    )
    (net (code "36") (name "Net-(U4-DELAY)") (class "Default")
      (node (ref "C3") (pin "2") (pinfunction "2_2") (pintype "passive"))
      (node (ref "U4") (pin "5") (pinfunction "DELAY_5") (pintype "bidirectional"))
    )
    (net (code "37") (name "Net-(U4-~{FAULT})") (class "Default")
      (node (ref "TP2") (pin "TP") (pinfunction "TP_TP") (pintype "input"))
      (node (ref "U4") (pin "3") (pinfunction "~{FAULT}_3") (pintype "output"))
    )
    (net (code "38") (name "PACK_INT") (class "Default")
      (node (ref "C21") (pin "2") (pinfunction "2_2") (pintype "passive"))
      (node (ref "IC1") (pin "6") (pinfunction "IO15_6") (pintype "bidirectional"))
      (node (ref "R25") (pin "2") (pinfunction "2_2") (pintype "passive"))
      (node (ref "U$24") (pin "P$10") (pinfunction "10_P$10") (pintype "passive"))
    )
    (net (code "39") (name "PACK_N_RESET") (class "Default")
      (node (ref "C49") (pin "2") (pinfunction "2_2") (pintype "passive"))
      (node (ref "C7") (pin "2") (pinfunction "2_2") (pintype "passive"))
      (node (ref "C8") (pin "2") (pinfunction "2_2") (pintype "passive"))
      (node (ref "IC1") (pin "15") (pinfunction "RST_15") (pintype "bidirectional"))
      (node (ref "R28") (pin "1") (pinfunction "1_1") (pintype "passive"))
      (node (ref "U$24") (pin "P$14") (pinfunction "14_P$14") (pintype "passive"))
      (node (ref "U1") (pin "12") (pinfunction "RES_12") (pintype "bidirectional"))
    )
    (net (code "40") (name "POWER_PDO2") (class "Default")
      (node (ref "R16") (pin "2") (pinfunction "2_2") (pintype "passive"))
      (node (ref "U$1") (pin "20") (pinfunction "POWER_OK2_20") (pintype "bidirectional"))
    )
    (net (code "41") (name "POWER_PDO3") (class "Default")
      (node (ref "R7") (pin "2") (pinfunction "2_2") (pintype "passive"))
      (node (ref "U$1") (pin "14") (pinfunction "POWER_OK3_14") (pintype "bidirectional"))
    )
    (net (code "42") (name "RR_A") (class "Default")
      (node (ref "C23") (pin "2") (pinfunction "2_2") (pintype "passive"))
      (node (ref "RSW1") (pin "A") (pinfunction "A_A") (pintype "bidirectional"))
      (node (ref "U$24") (pin "P$9") (pinfunction "9_P$9") (pintype "passive"))
    )
    (net (code "43") (name "RR_B") (class "Default")
      (node (ref "C24") (pin "2") (pinfunction "2_2") (pintype "passive"))
      (node (ref "RSW1") (pin "B") (pinfunction "B_B") (pintype "bidirectional"))
      (node (ref "U$24") (pin "P$7") (pinfunction "7_P$7") (pintype "passive"))
    )
    (net (code "44") (name "RR_E") (class "Default")
      (node (ref "C22") (pin "2") (pinfunction "2_2") (pintype "passive"))
      (node (ref "RSW1") (pin "SW2") (pinfunction "E_SW2") (pintype "bidirectional"))
      (node (ref "U$24") (pin "P$11") (pinfunction "11_P$11") (pintype "passive"))
    )
    (net (code "45") (name "RXD{slash}I2C") (class "Default")
      (node (ref "U$17") (pin "3") (pinfunction "P$3_3") (pintype "bidirectional"))
    )
    (net (code "46") (name "RXD{slash}I2S") (class "Default")
      (node (ref "IC1") (pin "11") (pinfunction "RXD_11") (pintype "bidirectional"))
      (node (ref "R17") (pin "2") (pinfunction "2_2") (pintype "passive"))
      (node (ref "U$14") (pin "TP") (pinfunction "TP_TP") (pintype "input"))
    )
    (net (code "47") (name "SCL") (class "Default")
      (node (ref "U$1") (pin "7") (pinfunction "SCL_7") (pintype "bidirectional"))
      (node (ref "U$23") (pin "TP") (pinfunction "TP_TP") (pintype "input"))
    )
    (net (code "48") (name "SDA") (class "Default")
      (node (ref "U$1") (pin "8") (pinfunction "SDA_8") (pintype "bidirectional"))
      (node (ref "U$22") (pin "TP") (pinfunction "TP_TP") (pintype "input"))
    )
    (net (code "49") (name "TXD") (class "Default")
      (node (ref "IC1") (pin "12") (pinfunction "TXD_12") (pintype "bidirectional"))
      (node (ref "R3") (pin "2") (pinfunction "2_2") (pintype "passive"))
      (node (ref "U$17") (pin "2") (pinfunction "P$2_2") (pintype "bidirectional"))
      (node (ref "U$8") (pin "TP") (pinfunction "TP_TP") (pintype "input"))
    )
    (net (code "50") (name "USB_CLK") (class "Default")
      (node (ref "IC1") (pin "3") (pinfunction "IO14_3") (pintype "bidirectional"))
      (node (ref "U1") (pin "13") (pinfunction "SCK_13") (pintype "bidirectional"))
    )
    (net (code "51") (name "USB_CS") (class "Default")
      (node (ref "IC1") (pin "7") (pinfunction "IO2_7") (pintype "bidirectional"))
      (node (ref "U1") (pin "14") (pinfunction "SS_14") (pintype "bidirectional"))
    )
    (net (code "52") (name "USB_INT{slash}GPIO0") (class "Default")
      (node (ref "IC1") (pin "8") (pinfunction "IO0_8") (pintype "bidirectional"))
      (node (ref "J3") (pin "2") (pinfunction "2_2") (pintype "passive"))
      (node (ref "R29") (pin "2") (pinfunction "2_2") (pintype "passive"))
      (node (ref "U$16") (pin "TP") (pinfunction "TP_TP") (pintype "input"))
      (node (ref "U1") (pin "18") (pinfunction "INT_18") (pintype "bidirectional"))
    )
    (net (code "53") (name "USB_SIMO") (class "Default")
      (node (ref "IC1") (pin "5") (pinfunction "IO13_5") (pintype "bidirectional"))
      (node (ref "U1") (pin "16") (pinfunction "MOSI_16") (pintype "bidirectional"))
    )
    (net (code "54") (name "USB_SOMI") (class "Default")
      (node (ref "IC1") (pin "4") (pinfunction "IO12_4") (pintype "bidirectional"))
      (node (ref "U1") (pin "15") (pinfunction "MISO_15") (pintype "bidirectional"))
    )
    (net (code "55") (name "VBUS") (class "Default")
      (node (ref "C11") (pin "2") (pinfunction "2_2") (pintype "passive"))
      (node (ref "R2") (pin "1") (pinfunction "1_1") (pintype "passive"))
      (node (ref "R4") (pin "2") (pinfunction "2_2") (pintype "passive"))
      (node (ref "U$1") (pin "24") (pinfunction "VDD_24") (pintype "bidirectional"))
      (node (ref "U$10") (pin "1") (pinfunction "S1_1") (pintype "bidirectional"))
      (node (ref "U$10") (pin "2") (pinfunction "S2_2") (pintype "bidirectional"))
      (node (ref "U$10") (pin "3") (pinfunction "S3_3") (pintype "bidirectional"))
      (node (ref "U$25") (pin "TP") (pinfunction "TP_TP") (pintype "input"))
      (node (ref "U$27") (pin "V1") (pinfunction "VBUS1_V1") (pintype "bidirectional"))
      (node (ref "U$27") (pin "V2") (pinfunction "VBUS2_V2") (pintype "bidirectional"))
      (node (ref "U$27") (pin "V3") (pinfunction "VBUS3_V3") (pintype "bidirectional"))
      (node (ref "U$27") (pin "V4") (pinfunction "VBUS4_V4") (pintype "bidirectional"))
      (node (ref "U$5") (pin "C") (pinfunction "C_C") (pintype "passive"))
    )
    (net (code "56") (name "VBUS_EN_SNK") (class "Default")
      (node (ref "R5") (pin "1") (pinfunction "1_1") (pintype "passive"))
      (node (ref "U$1") (pin "16") (pinfunction "VBUS_EN_SNK_16") (pintype "bidirectional"))
    )
    (net (code "57") (name "VBUS_MIDI") (class "Default")
      (node (ref "C14") (pin "2") (pinfunction "2_2") (pintype "passive"))
      (node (ref "C17") (pin "2") (pinfunction "2_2") (pintype "passive"))
      (node (ref "C19") (pin "2") (pinfunction "2_2") (pintype "passive"))
      (node (ref "C20") (pin "2") (pinfunction "2_2") (pintype "passive"))
      (node (ref "R23") (pin "1") (pinfunction "1_1") (pintype "passive"))
      (node (ref "U$6") (pin "V1") (pinfunction "VBUS1_V1") (pintype "bidirectional"))
      (node (ref "U$6") (pin "V2") (pinfunction "VBUS2_V2") (pintype "bidirectional"))
      (node (ref "U$6") (pin "V3") (pinfunction "VBUS3_V3") (pintype "bidirectional"))
      (node (ref "U$6") (pin "V4") (pinfunction "VBUS4_V4") (pintype "bidirectional"))
      (node (ref "U1") (pin "22") (pinfunction "VBCOMP_22") (pintype "bidirectional"))
      (node (ref "U4") (pin "7") (pinfunction "OUT_7") (pintype "output"))
    )
    (net (code "58") (name "VCC") (class "Default")
      (node (ref "C1") (pin "1") (pinfunction "1_1") (pintype "passive"))
      (node (ref "C12") (pin "2") (pinfunction "2_2") (pintype "passive"))
      (node (ref "C13") (pin "2") (pinfunction "2_2") (pintype "passive"))
      (node (ref "C18") (pin "2") (pinfunction "2_2") (pintype "passive"))
      (node (ref "C2") (pin "1") (pinfunction "1_1") (pintype "passive"))
      (node (ref "IC1") (pin "1") (pinfunction "3V3_1") (pintype "power_in"))
      (node (ref "R1") (pin "2") (pinfunction "2_2") (pintype "passive"))
      (node (ref "R28") (pin "2") (pinfunction "2_2") (pintype "passive"))
      (node (ref "R29") (pin "1") (pinfunction "1_1") (pintype "passive"))
      (node (ref "R8") (pin "2") (pinfunction "2_2") (pintype "passive"))
      (node (ref "U$19") (pin "TP") (pinfunction "TP_TP") (pintype "input"))
      (node (ref "U$24") (pin "P$13") (pinfunction "13_P$13") (pintype "passive"))
      (node (ref "U1") (pin "2") (pinfunction "VL_2") (pintype "bidirectional"))
      (node (ref "U1") (pin "23") (pinfunction "VCC_23") (pintype "bidirectional"))
      (node (ref "U2") (pin "12") (pinfunction "VDD_12") (pintype "power_in"))
    )
    (net (code "59") (name "VDD") (class "Default")
      (node (ref "C25") (pin "2") (pinfunction "2_2") (pintype "passive"))
      (node (ref "U$24") (pin "P$1") (pinfunction "1_P$1") (pintype "passive"))
      (node (ref "U$24") (pin "P$3") (pinfunction "3_P$3") (pintype "passive"))
      (node (ref "U4") (pin "2") (pinfunction "DIAG_EN_2") (pintype "input"))
      (node (ref "U4") (pin "8") (pinfunction "VS_8") (pintype "power_in"))
    )
    (net (code "60") (name "VREG_2V7") (class "Default")
      (node (ref "C9") (pin "2") (pinfunction "2_2") (pintype "passive"))
      (node (ref "U$1") (pin "23") (pinfunction "VREG_2V7_23") (pintype "bidirectional"))
    )
    (net (code "61") (name "VSNK") (class "Default")
      (node (ref "C6") (pin "1") (pinfunction "1_1") (pintype "passive"))
      (node (ref "D2") (pin "2") (pinfunction "ANODE_2") (pintype "bidirectional"))
      (node (ref "J1") (pin "1") (pinfunction "1_1") (pintype "bidirectional"))
      (node (ref "R11") (pin "1") (pinfunction "1_1") (pintype "passive"))
      (node (ref "U$10") (pin "5") (pinfunction "D1_5") (pintype "bidirectional"))
      (node (ref "U$10") (pin "6") (pinfunction "D2_6") (pintype "bidirectional"))
      (node (ref "U$10") (pin "7") (pinfunction "D3_7") (pintype "bidirectional"))
      (node (ref "U$10") (pin "8") (pinfunction "D4_8") (pintype "bidirectional"))
      (node (ref "U$12") (pin "C") (pinfunction "C_C") (pintype "passive"))
    )
    (net (code "62") (name "unconnected-(U$1-A_B_SIDE-Pad17)") (class "Default")
      (node (ref "U$1") (pin "17") (pinfunction "A_B_SIDE_17") (pintype "bidirectional"))
    )
    (net (code "63") (name "unconnected-(U$3-P$3-Pad3)") (class "Default")
      (node (ref "U$3") (pin "3") (pinfunction "P$3_3") (pintype "bidirectional"))
    )
    (net (code "64") (name "unconnected-(U$27-PadD+1)") (class "Default")
      (node (ref "U$27") (pin "D+1") (pinfunction "D+1_D+1") (pintype "bidirectional"))
    )
    (net (code "65") (name "unconnected-(U$27-PadD+2)") (class "Default")
      (node (ref "U$27") (pin "D+2") (pinfunction "D+2_D+2") (pintype "bidirectional"))
    )
    (net (code "66") (name "unconnected-(U$27-PadD-1)") (class "Default")
      (node (ref "U$27") (pin "D-1") (pinfunction "D-1_D-1") (pintype "bidirectional"))
    )
    (net (code "67") (name "unconnected-(U$27-PadD-2)") (class "Default")
      (node (ref "U$27") (pin "D-2") (pinfunction "D-2_D-2") (pintype "bidirectional"))
    )
    (net (code "68") (name "unconnected-(U1-GOUT0-Pad4)") (class "Default")
      (node (ref "U1") (pin "4") (pinfunction "GOUT0_4") (pintype "bidirectional"))
    )
    (net (code "69") (name "unconnected-(U1-GOUT1-Pad5)") (class "Default")
      (node (ref "U1") (pin "5") (pinfunction "GOUT1_5") (pintype "bidirectional"))
    )
    (net (code "70") (name "unconnected-(U1-GOUT2-Pad6)") (class "Default")
      (node (ref "U1") (pin "6") (pinfunction "GOUT2_6") (pintype "bidirectional"))
    )
    (net (code "71") (name "unconnected-(U1-GOUT3-Pad7)") (class "Default")
      (node (ref "U1") (pin "7") (pinfunction "GOUT3_7") (pintype "bidirectional"))
    )
    (net (code "72") (name "unconnected-(U1-GOUT4-Pad8)") (class "Default")
      (node (ref "U1") (pin "8") (pinfunction "GOUT4_8") (pintype "bidirectional"))
    )
    (net (code "73") (name "unconnected-(U1-GOUT5-Pad9)") (class "Default")
      (node (ref "U1") (pin "9") (pinfunction "GOUT5_9") (pintype "bidirectional"))
    )
    (net (code "74") (name "unconnected-(U1-GOUT6-Pad10)") (class "Default")
      (node (ref "U1") (pin "10") (pinfunction "GOUT6_10") (pintype "bidirectional"))
    )
    (net (code "75") (name "unconnected-(U1-GOUT7-Pad11)") (class "Default")
      (node (ref "U1") (pin "11") (pinfunction "GOUT7_11") (pintype "bidirectional"))
    )
    (net (code "76") (name "unconnected-(U1-GPIN3-Pad29)") (class "Default")
      (node (ref "U1") (pin "29") (pinfunction "GPIN3_29") (pintype "bidirectional"))
    )
    (net (code "77") (name "unconnected-(U1-GPIN4-Pad30)") (class "Default")
      (node (ref "U1") (pin "30") (pinfunction "GPIN4_30") (pintype "bidirectional"))
    )
    (net (code "78") (name "unconnected-(U1-GPIN5-Pad31)") (class "Default")
      (node (ref "U1") (pin "31") (pinfunction "GPIN5_31") (pintype "bidirectional"))
    )
    (net (code "79") (name "unconnected-(U1-GPIN7-Pad1)") (class "Default")
      (node (ref "U1") (pin "1") (pinfunction "GPIN7_1") (pintype "bidirectional"))
    )
    (net (code "80") (name "unconnected-(U1-GPX-Pad17)") (class "Default")
      (node (ref "U1") (pin "17") (pinfunction "GPX_17") (pintype "bidirectional"))
    )
    (net (code "81") (name "unconnected-(U2-ADDR-Pad5)") (class "Default")
      (node (ref "U2") (pin "5") (pinfunction "ADDR_5") (pintype "input"))
    )
    (net (code "82") (name "unconnected-(U2-INT_N_OUT3-Pad6)") (class "Default")
      (node (ref "U2") (pin "6") (pinfunction "INT_N_OUT3_6") (pintype "open_collector"))
    )
    (net (code "83") (name "unconnected-(U2-PORT-Pad3)") (class "Default")
      (node (ref "U2") (pin "3") (pinfunction "PORT_3") (pintype "input"))
    )
    (net (code "84") (name "unconnected-(U2-SCL_OUT2-Pad8)") (class "Default")
      (node (ref "U2") (pin "8") (pinfunction "SCL_OUT2_8") (pintype "bidirectional"))
    )
    (net (code "85") (name "unconnected-(U2-SDA_OUT1-Pad7)") (class "Default")
      (node (ref "U2") (pin "7") (pinfunction "SDA_OUT1_7") (pintype "bidirectional"))
    )
  )
)
